# bpf.net
KiCad netlist of a schematic drawn in EAGLE
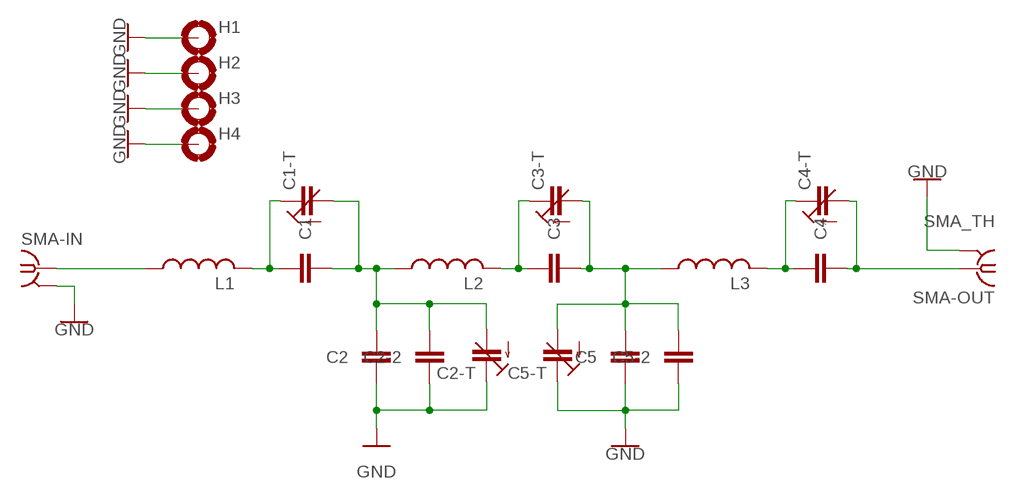
[diagram p0: schematic, sheet 1]

(export (version "E")
  (design (tool "Eeschema 10.0.6"))
  (components
    (comp (ref "C1")
      (value "C_0805_PTH")
      (footprint "eagle-import:C0805K")
      (libsource (lib "eagle-import") (part "C_0805_PTH"))
    )
    (comp (ref "C1-T")
      (value "C_TRIM_TH")
      (footprint "eagle-import:CTRIM3050.505")
      (libsource (lib "eagle-import") (part "C_TRIM_TH"))
    )
    (comp (ref "C2")
      (value "C_0805_PTH")
      (footprint "eagle-import:C0805K")
      (libsource (lib "eagle-import") (part "C_0805_PTH"))
    )
    (comp (ref "C2-2")
      (value "C_0805_PTH")
      (footprint "eagle-import:C0805K")
      (libsource (lib "eagle-import") (part "C_0805_PTH"))
    )
    (comp (ref "C2-T")
      (value "C_TRIM_TH")
      (footprint "eagle-import:CTRIM3050.505")
      (libsource (lib "eagle-import") (part "C_TRIM_TH"))
    )
    (comp (ref "C3")
      (value "C_0805_PTH")
      (footprint "eagle-import:C0805K")
      (libsource (lib "eagle-import") (part "C_0805_PTH"))
    )
    (comp (ref "C3-T")
      (value "C_TRIM_TH")
      (footprint "eagle-import:CTRIM3050.505")
      (libsource (lib "eagle-import") (part "C_TRIM_TH"))
    )
    (comp (ref "C4")
      (value "C_0805_PTH")
      (footprint "eagle-import:C0805K")
      (libsource (lib "eagle-import") (part "C_0805_PTH"))
    )
    (comp (ref "C4-T")
      (value "C_TRIM_TH")
      (footprint "eagle-import:CTRIM3050.505")
      (libsource (lib "eagle-import") (part "C_TRIM_TH"))
    )
    (comp (ref "C5")
      (value "C_0805_PTH")
      (footprint "eagle-import:C0805K")
      (libsource (lib "eagle-import") (part "C_0805_PTH"))
    )
    (comp (ref "C5-2")
      (value "C_0805_PTH")
      (footprint "eagle-import:C0805K")
      (libsource (lib "eagle-import") (part "C_0805_PTH"))
    )
    (comp (ref "C5-T")
      (value "C_TRIM_TH")
      (footprint "eagle-import:CTRIM3050.505")
      (libsource (lib "eagle-import") (part "C_TRIM_TH"))
    )
    (comp (ref "H1")
      (value "MOUNT-PAD-ROUND3.0")
      (footprint "eagle-import:3,0-PAD")
      (libsource (lib "eagle-import") (part "MOUNT-PAD-ROUND3.0"))
    )
    (comp (ref "H2")
      (value "MOUNT-PAD-ROUND3.0")
      (footprint "eagle-import:3,0-PAD")
      (libsource (lib "eagle-import") (part "MOUNT-PAD-ROUND3.0"))
    )
    (comp (ref "H3")
      (value "MOUNT-PAD-ROUND3.0")
      (footprint "eagle-import:3,0-PAD")
      (libsource (lib "eagle-import") (part "MOUNT-PAD-ROUND3.0"))
    )
    (comp (ref "H4")
      (value "MOUNT-PAD-ROUND3.0")
      (footprint "eagle-import:3,0-PAD")
      (libsource (lib "eagle-import") (part "MOUNT-PAD-ROUND3.0"))
    )
    (comp (ref "L1")
      (value "L_0805_PTH")
      (footprint "eagle-import:M0805")
      (libsource (lib "eagle-import") (part "L_0805_PTH"))
    )
    (comp (ref "L2")
      (value "L_0805_PTH")
      (footprint "eagle-import:M0805")
      (libsource (lib "eagle-import") (part "L_0805_PTH"))
    )
    (comp (ref "L3")
      (value "L_0805_PTH")
      (footprint "eagle-import:M0805")
      (libsource (lib "eagle-import") (part "L_0805_PTH"))
    )
    (comp (ref "SMA-IN")
      (value "SMA-142-0711-821/826")
      (footprint "eagle-import:J502-ND-142-0711-821_826")
      (fields (field (name "MF") "JOHNSON COMPONENTS") (field (name "MPN") "142-0711-821"))
      (libsource (lib "eagle-import") (part "SMA-142-0711-821/826"))
    )
    (comp (ref "SMA-OUT")
      (value "SMA_TH")
      (footprint "eagle-import:BU-SMA-V")
      (libsource (lib "eagle-import") (part "SMA_TH"))
    )
  )
  (nets
    (net (code "1") (name "GND") (class "Default")
      (node (ref "C2") (pin "1") (pinfunction "1_1") (pintype "passive"))
      (node (ref "C2") (pin "P$1") (pinfunction "1_P$1") (pintype "passive"))
      (node (ref "C2-2") (pin "1") (pinfunction "1_1") (pintype "passive"))
      (node (ref "C2-2") (pin "P$1") (pinfunction "1_P$1") (pintype "passive"))
      (node (ref "C2-T") (pin "2") (pinfunction "E_2") (pintype "passive"))
      (node (ref "C5") (pin "1") (pinfunction "1_1") (pintype "passive"))
      (node (ref "C5") (pin "P$1") (pinfunction "1_P$1") (pintype "passive"))
      (node (ref "C5-2") (pin "1") (pinfunction "1_1") (pintype "passive"))
      (node (ref "C5-2") (pin "P$1") (pinfunction "1_P$1") (pintype "passive"))
      (node (ref "C5-T") (pin "2") (pinfunction "E_2") (pintype "passive"))
      (node (ref "H1") (pin "B3,0") (pinfunction "MOUNT_B3,0") (pintype "passive"))
      (node (ref "H2") (pin "B3,0") (pinfunction "MOUNT_B3,0") (pintype "passive"))
      (node (ref "H3") (pin "B3,0") (pinfunction "MOUNT_B3,0") (pintype "passive"))
      (node (ref "H4") (pin "B3,0") (pinfunction "MOUNT_B3,0") (pintype "passive"))
      (node (ref "SMA-IN") (pin "G@1") (pinfunction "2_G@1") (pintype "passive"))
      (node (ref "SMA-IN") (pin "G@2") (pinfunction "2_G@2") (pintype "passive"))
      (node (ref "SMA-IN") (pin "G@3") (pinfunction "2_G@3") (pintype "passive"))
      (node (ref "SMA-IN") (pin "G@4") (pinfunction "2_G@4") (pintype "passive"))
      (node (ref "SMA-OUT") (pin "2") (pinfunction "GND_2") (pintype "passive"))
      (node (ref "SMA-OUT") (pin "3") (pinfunction "GND_3") (pintype "passive"))
      (node (ref "SMA-OUT") (pin "4") (pinfunction "GND_4") (pintype "passive"))
      (node (ref "SMA-OUT") (pin "5") (pinfunction "GND_5") (pintype "passive"))
    )
    (net (code "2") (name "Net-(C1-T-A)") (class "Default")
      (node (ref "C1") (pin "2") (pinfunction "2_2") (pintype "passive"))
      (node (ref "C1") (pin "P$2") (pinfunction "2_P$2") (pintype "passive"))
      (node (ref "C1-T") (pin "1") (pinfunction "A_1") (pintype "passive"))
      (node (ref "C2") (pin "2") (pinfunction "2_2") (pintype "passive"))
      (node (ref "C2") (pin "P$2") (pinfunction "2_P$2") (pintype "passive"))
      (node (ref "C2-2") (pin "2") (pinfunction "2_2") (pintype "passive"))
      (node (ref "C2-2") (pin "P$2") (pinfunction "2_P$2") (pintype "passive"))
      (node (ref "C2-T") (pin "1") (pinfunction "A_1") (pintype "passive"))
      (node (ref "L2") (pin "1") (pinfunction "1_1") (pintype "passive"))
      (node (ref "L2") (pin "P$1") (pinfunction "1_P$1") (pintype "passive"))
    )
    (net (code "3") (name "Net-(C1-T-E)") (class "Default")
      (node (ref "C1") (pin "1") (pinfunction "1_1") (pintype "passive"))
      (node (ref "C1") (pin "P$1") (pinfunction "1_P$1") (pintype "passive"))
      (node (ref "C1-T") (pin "2") (pinfunction "E_2") (pintype "passive"))
      (node (ref "L1") (pin "2") (pinfunction "2_2") (pintype "passive"))
      (node (ref "L1") (pin "P$2") (pinfunction "2_P$2") (pintype "passive"))
    )
    (net (code "4") (name "Net-(C3-T-A)") (class "Default")
      (node (ref "C3") (pin "2") (pinfunction "2_2") (pintype "passive"))
      (node (ref "C3") (pin "P$2") (pinfunction "2_P$2") (pintype "passive"))
      (node (ref "C3-T") (pin "1") (pinfunction "A_1") (pintype "passive"))
      (node (ref "C5") (pin "2") (pinfunction "2_2") (pintype "passive"))
      (node (ref "C5") (pin "P$2") (pinfunction "2_P$2") (pintype "passive"))
      (node (ref "C5-2") (pin "2") (pinfunction "2_2") (pintype "passive"))
      (node (ref "C5-2") (pin "P$2") (pinfunction "2_P$2") (pintype "passive"))
      (node (ref "C5-T") (pin "1") (pinfunction "A_1") (pintype "passive"))
      (node (ref "L3") (pin "1") (pinfunction "1_1") (pintype "passive"))
      (node (ref "L3") (pin "P$1") (pinfunction "1_P$1") (pintype "passive"))
    )
    (net (code "5") (name "Net-(C3-T-E)") (class "Default")
      (node (ref "C3") (pin "1") (pinfunction "1_1") (pintype "passive"))
      (node (ref "C3") (pin "P$1") (pinfunction "1_P$1") (pintype "passive"))
      (node (ref "C3-T") (pin "2") (pinfunction "E_2") (pintype "passive"))
      (node (ref "L2") (pin "2") (pinfunction "2_2") (pintype "passive"))
      (node (ref "L2") (pin "P$2") (pinfunction "2_P$2") (pintype "passive"))
    )
    (net (code "6") (name "Net-(C4-T-A)") (class "Default")
      (node (ref "C4") (pin "2") (pinfunction "2_2") (pintype "passive"))
      (node (ref "C4") (pin "P$2") (pinfunction "2_P$2") (pintype "passive"))
      (node (ref "C4-T") (pin "1") (pinfunction "A_1") (pintype "passive"))
      (node (ref "SMA-OUT") (pin "1") (pinfunction "1_1") (pintype "passive"))
    )
    (net (code "7") (name "Net-(C4-T-E)") (class "Default")
      (node (ref "C4") (pin "1") (pinfunction "1_1") (pintype "passive"))
      (node (ref "C4") (pin "P$1") (pinfunction "1_P$1") (pintype "passive"))
      (node (ref "C4-T") (pin "2") (pinfunction "E_2") (pintype "passive"))
      (node (ref "L3") (pin "2") (pinfunction "2_2") (pintype "passive"))
      (node (ref "L3") (pin "P$2") (pinfunction "2_P$2") (pintype "passive"))
    )
    (net (code "8") (name "Net-(L1-1-PadP$1)") (class "Default")
      (node (ref "L1") (pin "1") (pinfunction "1_1") (pintype "passive"))
      (node (ref "L1") (pin "P$1") (pinfunction "1_P$1") (pintype "passive"))
      (node (ref "SMA-IN") (pin "1") (pinfunction "1_1") (pintype "passive"))
    )
  )
)
